# Sheet1.net
KiCad netlist of a schematic drawn in Altium Designer
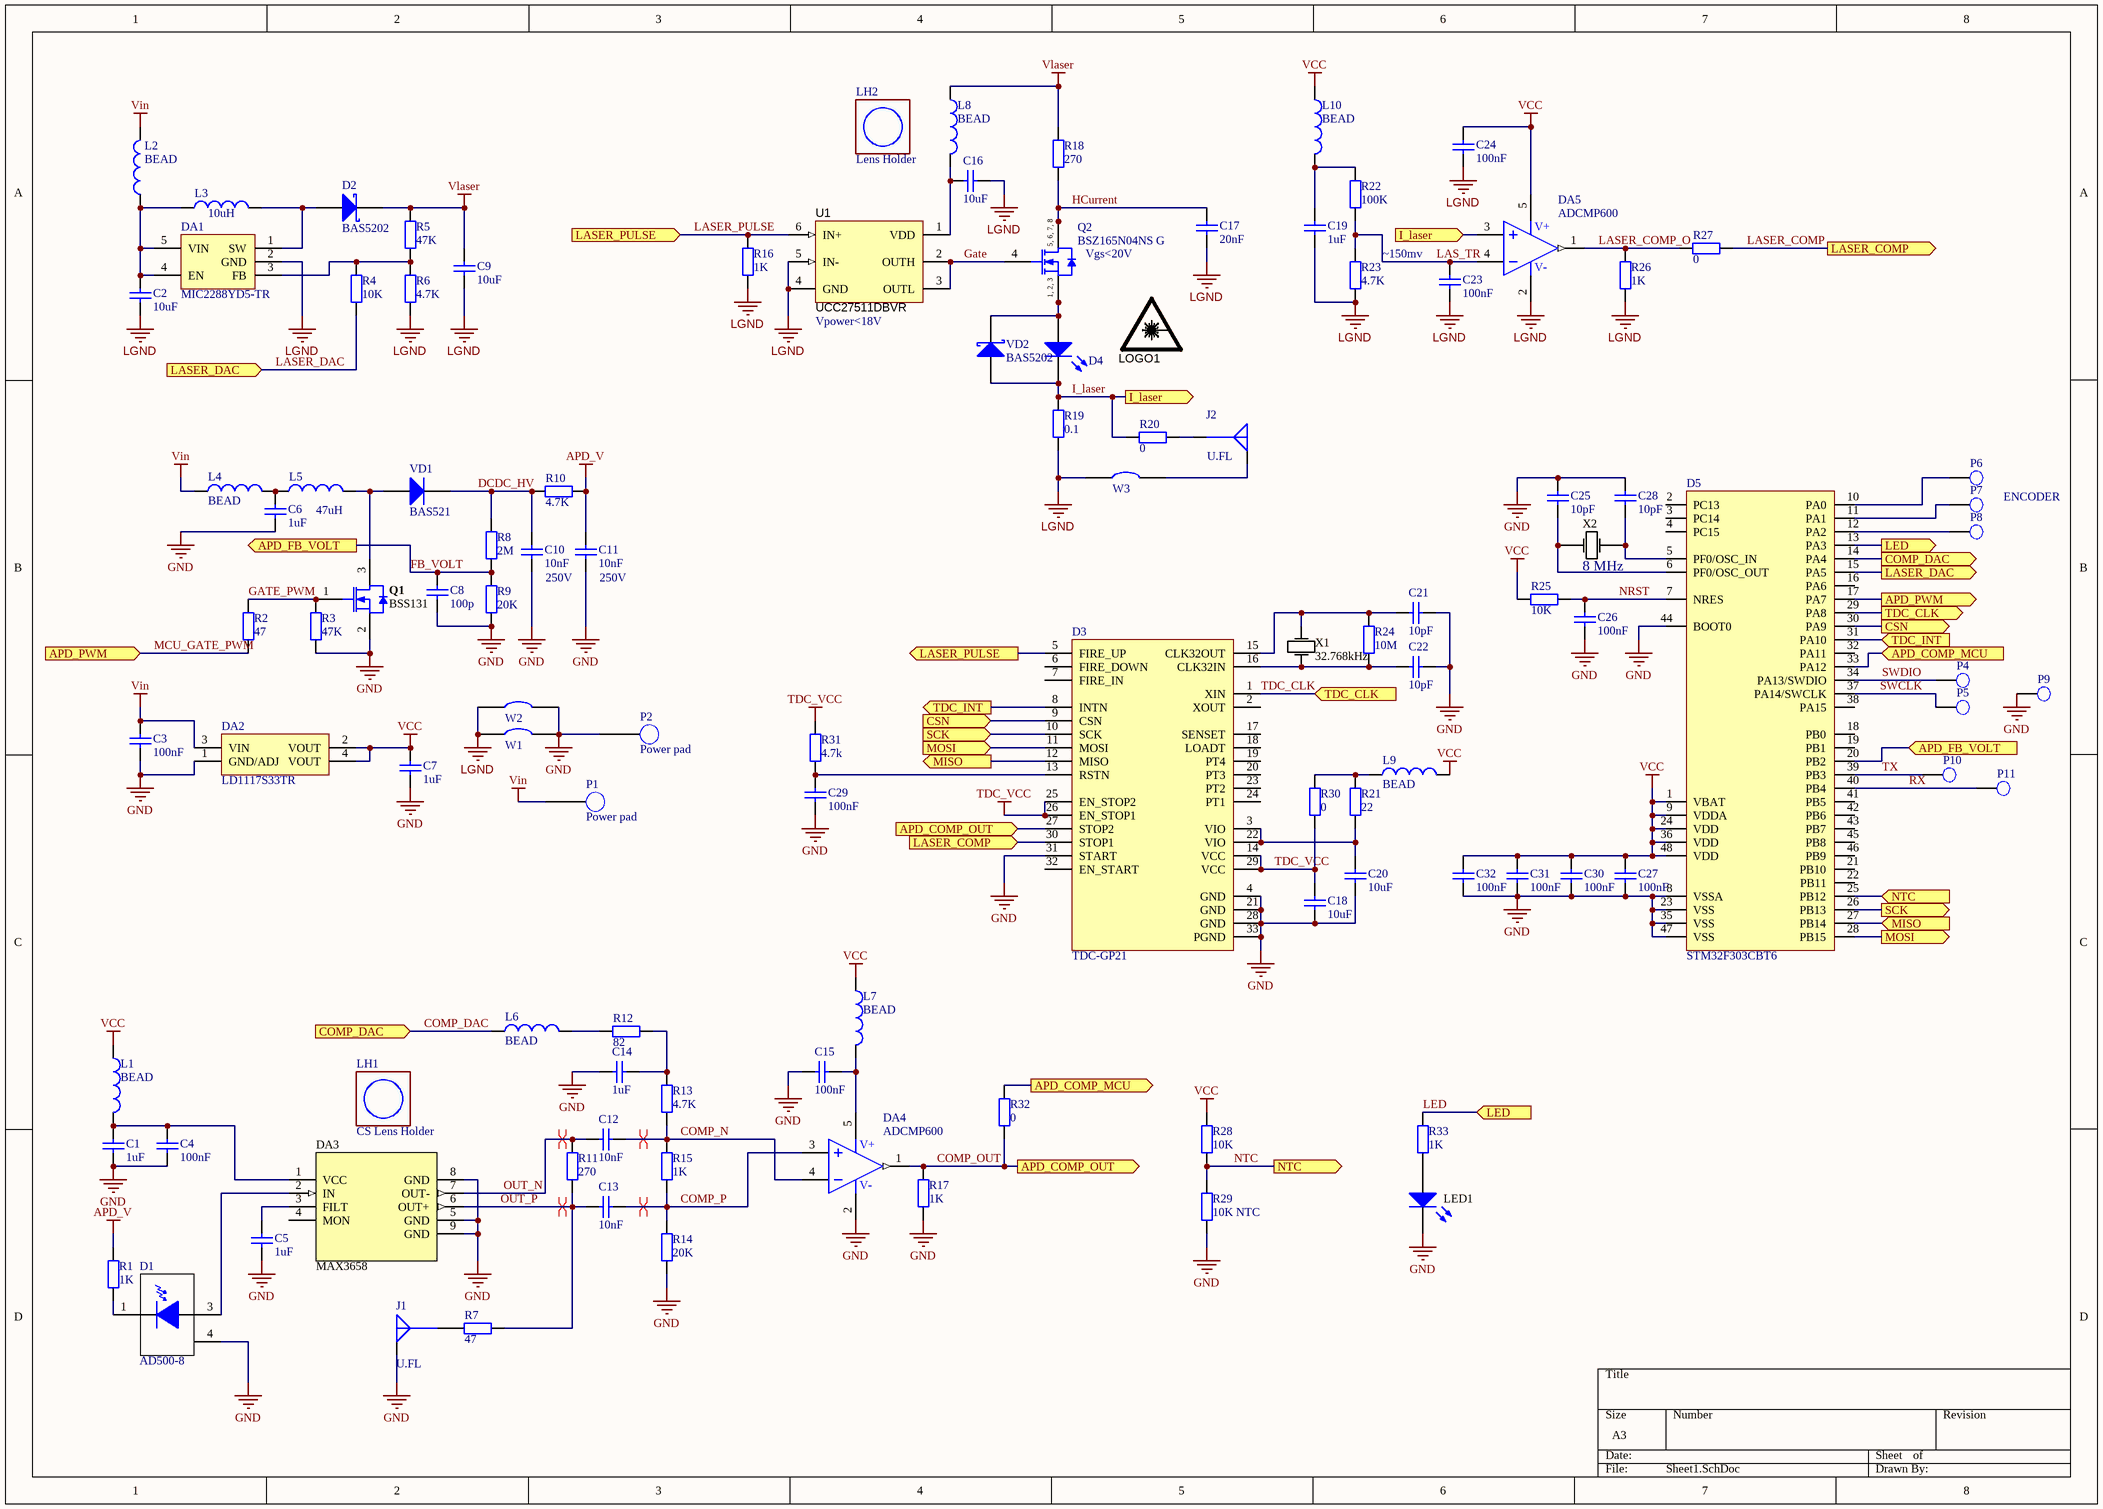
[diagram p0: Sheet1.SchDoc]

(export (version "E")
  (design (tool "Eeschema 10.0.6"))
  (components
    (comp (ref "C1")
      (value "1uF")
      (footprint "CAPC2012X135N")
      (description "Chip capacitor")
      (fields (field (name "VOLTAGE") "25V"))
      (libsource (lib "MyLibSch") (part "CC0805"))
    )
    (comp (ref "C2")
      (value "10uF")
      (footprint "CAPC1608X90N")
      (description "Chip capacitor")
      (fields (field (name "VOLTAGE") "25V"))
      (libsource (lib "MyLibSch") (part "CC0805"))
    )
    (comp (ref "C3")
      (value "100nF")
      (footprint "CAPC1608X90N")
      (description "Chip capacitor")
      (fields (field (name "VOLTAGE") "25V"))
      (libsource (lib "MyLibSch") (part "CC0805"))
    )
    (comp (ref "C4")
      (value "100nF")
      (footprint "CAPC1608X90N")
      (description "Chip capacitor")
      (fields (field (name "VOLTAGE") "25V"))
      (libsource (lib "MyLibSch") (part "CC0805"))
    )
    (comp (ref "C5")
      (value "1uF")
      (footprint "CAPC1608X90N")
      (description "Chip capacitor")
      (fields (field (name "VOLTAGE") "25V"))
      (libsource (lib "MyLibSch") (part "CC0805"))
    )
    (comp (ref "C6")
      (value "1uF")
      (footprint "CAPC2012X135N")
      (description "Chip capacitor")
      (fields (field (name "VOLTAGE") "25V"))
      (libsource (lib "MyLibSch") (part "CC0805"))
    )
    (comp (ref "C7")
      (value "1uF")
      (footprint "CAPC2012X135N")
      (description "Chip capacitor")
      (fields (field (name "VOLTAGE") "25V"))
      (libsource (lib "MyLibSch") (part "CC0805"))
    )
    (comp (ref "C8")
      (value "100p")
      (footprint "CAPC1608X90N")
      (description "Chip capacitor")
      (fields (field (name "VOLTAGE") "25V"))
      (libsource (lib "MyLibSch") (part "CC0805"))
    )
    (comp (ref "C9")
      (value "10uF")
      (footprint "CAPC1608X90N")
      (description "Chip capacitor")
      (fields (field (name "VOLTAGE") "25V"))
      (libsource (lib "MyLibSch") (part "CC0805"))
    )
    (comp (ref "C10")
      (value "10nF")
      (footprint "CAPC2012X135N")
      (description "Chip capacitor")
      (fields (field (name "VOLTAGE") "250V"))
      (libsource (lib "MyLibSch") (part "CC0805"))
    )
    (comp (ref "C11")
      (value "10nF")
      (footprint "CAPC2012X135N")
      (description "Chip capacitor")
      (fields (field (name "VOLTAGE") "250V"))
      (libsource (lib "MyLibSch") (part "CC0805"))
    )
    (comp (ref "C12")
      (value "10nF")
      (footprint "CAPC1608X90N")
      (description "Chip capacitor")
      (fields (field (name "VOLTAGE") "25V"))
      (libsource (lib "MyLibSch") (part "CC0805"))
    )
    (comp (ref "C13")
      (value "10nF")
      (footprint "CAPC1608X90N")
      (description "Chip capacitor")
      (fields (field (name "VOLTAGE") "25V"))
      (libsource (lib "MyLibSch") (part "CC0805"))
    )
    (comp (ref "C14")
      (value "1uF")
      (footprint "CAPC2012X135N")
      (description "Chip capacitor")
      (fields (field (name "VOLTAGE") "25V"))
      (libsource (lib "MyLibSch") (part "CC0805"))
    )
    (comp (ref "C15")
      (value "100nF")
      (footprint "CAPC1608X90N")
      (description "Chip capacitor")
      (fields (field (name "VOLTAGE") "25V"))
      (libsource (lib "MyLibSch") (part "CC0805"))
    )
    (comp (ref "C16")
      (value "10uF")
      (footprint "CAPC1608X90N")
      (description "Chip capacitor")
      (fields (field (name "VOLTAGE") "25V"))
      (libsource (lib "MyLibSch") (part "CC0805"))
    )
    (comp (ref "C17")
      (value "20nF")
      (footprint "CAPC1608X90N")
      (description "Chip capacitor")
      (fields (field (name "VOLTAGE") "25V"))
      (libsource (lib "MyLibSch") (part "CC0805"))
    )
    (comp (ref "C18")
      (value "10uF")
      (footprint "CAPC1608X90N")
      (description "Chip capacitor")
      (fields (field (name "VOLTAGE") "25V"))
      (libsource (lib "MyLibSch") (part "CC0805"))
    )
    (comp (ref "C19")
      (value "1uF")
      (footprint "CAPC2012X135N")
      (description "Chip capacitor")
      (fields (field (name "VOLTAGE") "25V"))
      (libsource (lib "MyLibSch") (part "CC0805"))
    )
    (comp (ref "C20")
      (value "10uF")
      (footprint "CAPC1608X90N")
      (description "Chip capacitor")
      (fields (field (name "VOLTAGE") "25V"))
      (libsource (lib "MyLibSch") (part "CC0805"))
    )
    (comp (ref "C21")
      (value "10pF")
      (footprint "CAPC1608X90N")
      (description "Chip capacitor")
      (fields (field (name "VOLTAGE") "25V"))
      (libsource (lib "MyLibSch") (part "CC0805"))
    )
    (comp (ref "C22")
      (value "10pF")
      (footprint "CAPC1608X90N")
      (description "Chip capacitor")
      (fields (field (name "VOLTAGE") "25V"))
      (libsource (lib "MyLibSch") (part "CC0805"))
    )
    (comp (ref "C23")
      (value "100nF")
      (footprint "CAPC1608X90N")
      (description "Chip capacitor")
      (fields (field (name "VOLTAGE") "25V"))
      (libsource (lib "MyLibSch") (part "CC0805"))
    )
    (comp (ref "C24")
      (value "100nF")
      (footprint "CAPC1608X90N")
      (description "Chip capacitor")
      (fields (field (name "VOLTAGE") "25V"))
      (libsource (lib "MyLibSch") (part "CC0805"))
    )
    (comp (ref "C25")
      (value "10pF")
      (footprint "CAPC1608X90N")
      (description "Chip capacitor")
      (fields (field (name "VOLTAGE") "25V"))
      (libsource (lib "MyLibSch") (part "CC0805"))
    )
    (comp (ref "C26")
      (value "100nF")
      (footprint "CAPC1608X90N")
      (description "Chip capacitor")
      (fields (field (name "VOLTAGE") "25V"))
      (libsource (lib "MyLibSch") (part "CC0805"))
    )
    (comp (ref "C27")
      (value "100nF")
      (footprint "CAPC1608X90N")
      (description "Chip capacitor")
      (fields (field (name "VOLTAGE") "25V"))
      (libsource (lib "MyLibSch") (part "CC0805"))
    )
    (comp (ref "C28")
      (value "10pF")
      (footprint "CAPC1608X90N")
      (description "Chip capacitor")
      (fields (field (name "VOLTAGE") "25V"))
      (libsource (lib "MyLibSch") (part "CC0805"))
    )
    (comp (ref "C29")
      (value "100nF")
      (footprint "CAPC1608X90N")
      (description "Chip capacitor")
      (fields (field (name "VOLTAGE") "25V"))
      (libsource (lib "MyLibSch") (part "CC0805"))
    )
    (comp (ref "C30")
      (value "100nF")
      (footprint "CAPC1608X90N")
      (description "Chip capacitor")
      (fields (field (name "VOLTAGE") "25V"))
      (libsource (lib "MyLibSch") (part "CC0805"))
    )
    (comp (ref "C31")
      (value "100nF")
      (footprint "CAPC1608X90N")
      (description "Chip capacitor")
      (fields (field (name "VOLTAGE") "25V"))
      (libsource (lib "MyLibSch") (part "CC0805"))
    )
    (comp (ref "C32")
      (value "100nF")
      (footprint "CAPC1608X90N")
      (description "Chip capacitor")
      (fields (field (name "VOLTAGE") "25V"))
      (libsource (lib "MyLibSch") (part "CC0805"))
    )
    (comp (ref "D1")
      (value "AD500-8")
      (footprint "AD500-8")
      (description "APD photodiode")
      (libsource (lib "lcd_lib") (part "AD500-8"))
    )
    (comp (ref "D2")
      (value "BAS5202")
      (footprint "SOD523F")
      (description "Schottky Diode")
      (fields (field (name "PUBLISHER") "Altium Limited"))
      (libsource (lib "Miscellaneous Devices") (part "D Schottky"))
    )
    (comp (ref "D3")
      (value "TDC-GP21")
      (footprint "QFN32 5x5mm")
      (description "TDC")
      (libsource (lib "lcd_lib") (part "TDC_GP21"))
    )
    (comp (ref "D4")
      (value "Laser")
      (footprint "SPL_PL90")
      (description "TO-18 Laser")
      (libsource (lib "lcd_lib") (part "TO-18 Laser"))
    )
    (comp (ref "D5")
      (value "STM32F303CBT6")
      (footprint "LQFP-48_N")
      (description "Microcontroller")
      (libsource (lib "lcd_lib") (part "STM32F3_LQFP48"))
    )
    (comp (ref "DA1")
      (value "MIC2288YD5-TR")
      (footprint "SOT23-5")
      (description "Step Up")
      (libsource (lib "lcd_lib") (part "MIC2288"))
    )
    (comp (ref "DA2")
      (value "LD1117S33TR")
      (footprint "SOT223")
      (description "LOW DROP FIXED AND ADJUSTABLE  POSITIVE VOLTAGE REGULATORS")
      (libsource (lib "MyLibSch") (part "LD1117S"))
    )
    (comp (ref "DA3")
      (value "MAX3658")
      (footprint "TDFN-8_0.65")
      (description "Transimpedance Amp")
      (fields (field (name "PART NUMBER") "AD7278"))
      (libsource (lib "lcd_lib") (part "MAX3658"))
    )
    (comp (ref "DA4")
      (value "ADCMP600")
      (footprint "SOT23-5")
      (description "Fast comparator")
      (libsource (lib "lcd_lib") (part "ADCMP600"))
    )
    (comp (ref "DA5")
      (value "ADCMP600")
      (footprint "SOT23-5")
      (description "Fast comparator")
      (libsource (lib "lcd_lib") (part "ADCMP600"))
    )
    (comp (ref "J1")
      (value "U.FL")
      (footprint "TE C-1909763")
      (libsource (lib "RF Connector") (part "RF Connector - SMA"))
    )
    (comp (ref "J2")
      (value "U.FL")
      (footprint "TE C-1909763")
      (libsource (lib "RF Connector") (part "RF Connector - SMA"))
    )
    (comp (ref "L1")
      (value "BEAD")
      (footprint "INDC1608N")
      (description "Ferrit Bead")
      (libsource (lib "MyLibSch") (part "BEAD"))
    )
    (comp (ref "L2")
      (value "BEAD")
      (footprint "INDC1608N")
      (description "Ferrit Bead")
      (libsource (lib "MyLibSch") (part "BEAD"))
    )
    (comp (ref "L3")
      (value "10uH")
      (footprint "MyLibPcb:V0805HD")
      (description "Inductor")
      (fields (field (name "PUBLISHER") "Altium Limited"))
      (libsource (lib "Miscellaneous Devices") (part "Inductor"))
    )
    (comp (ref "L4")
      (value "BEAD")
      (footprint "INDC1608N")
      (description "Ferrit Bead")
      (libsource (lib "MyLibSch") (part "BEAD"))
    )
    (comp (ref "L5")
      (value "47uH")
      (footprint "INDC3216")
      (description "Inductor")
      (fields (field (name "PUBLISHER") "Altium Limited"))
      (libsource (lib "Miscellaneous Devices") (part "Inductor"))
    )
    (comp (ref "L6")
      (value "BEAD")
      (footprint "INDC1608N")
      (description "Ferrit Bead")
      (libsource (lib "MyLibSch") (part "BEAD"))
    )
    (comp (ref "L7")
      (value "BEAD")
      (footprint "INDC1608N")
      (description "Ferrit Bead")
      (libsource (lib "MyLibSch") (part "BEAD"))
    )
    (comp (ref "L8")
      (value "BEAD")
      (footprint "INDC1608N")
      (description "Ferrit Bead")
      (libsource (lib "MyLibSch") (part "BEAD"))
    )
    (comp (ref "L9")
      (value "BEAD")
      (footprint "INDC1608N")
      (description "Ferrit Bead")
      (libsource (lib "MyLibSch") (part "BEAD"))
    )
    (comp (ref "L10")
      (value "BEAD")
      (footprint "INDC1608N")
      (description "Ferrit Bead")
      (libsource (lib "MyLibSch") (part "BEAD"))
    )
    (comp (ref "LED1")
      (value "LED")
      (footprint "PcbLib3:LED_0603")
      (description "LED_0603")
      (libsource (lib "lcd_lib") (part "LED_0603"))
    )
    (comp (ref "LH1")
      (value "CS Lens Holder")
      (footprint "Lens Holder CS")
      (description "M12 Lens Holder")
      (libsource (lib "lcd_lib") (part "CS Lens Holder"))
    )
    (comp (ref "LH2")
      (value "Lens Holder")
      (footprint "LENS_HOLDER_20MM_ADJ")
      (description "M12 Lens Holder")
      (libsource (lib "lcd_lib") (part "M12 Lens Holder"))
    )
    (comp (ref "LOGO1")
      (value "LASER RADIATION")
      (footprint "LaserWarning_Small")
      (description "Laser Warning Symbol")
      (fields (field (name "SYMBOLCREATOR") "a0412235") (field (name "PUBLISHER") "Texas Instruments"))
      (libsource (lib "Logos") (part "Laser_Warning"))
    )
    (comp (ref "P1")
      (value "Power pad")
      (footprint "Ext_power_pad")
      (description "Pad for wire")
      (libsource (lib "lcd_lib") (part "Power_pad"))
    )
    (comp (ref "P2")
      (value "Power pad")
      (footprint "Ext_power_pad")
      (description "Pad for wire")
      (libsource (lib "lcd_lib") (part "Power_pad"))
    )
    (comp (ref "P4")
      (value "Pad")
      (footprint "PcbLib3:Ext_pad_2")
      (description "Pad for wire")
      (libsource (lib "lcd_lib") (part "Ext Pad"))
    )
    (comp (ref "P5")
      (value "Pad")
      (footprint "PcbLib3:Ext_pad_2")
      (description "Pad for wire")
      (libsource (lib "lcd_lib") (part "Ext Pad"))
    )
    (comp (ref "P6")
      (value "Pad")
      (footprint "PcbLib3:Ext_pad_2")
      (description "Pad for wire")
      (libsource (lib "lcd_lib") (part "Ext Pad"))
    )
    (comp (ref "P7")
      (value "Pad")
      (footprint "PcbLib3:Ext_pad_2")
      (description "Pad for wire")
      (libsource (lib "lcd_lib") (part "Ext Pad"))
    )
    (comp (ref "P8")
      (value "Pad")
      (footprint "PcbLib3:Ext_pad_2")
      (description "Pad for wire")
      (libsource (lib "lcd_lib") (part "Ext Pad"))
    )
    (comp (ref "P9")
      (value "Pad")
      (footprint "PcbLib3:Ext_pad_2")
      (description "Pad for wire")
      (libsource (lib "lcd_lib") (part "Ext Pad"))
    )
    (comp (ref "P10")
      (value "Pad")
      (footprint "PcbLib3:Ext_pad_2")
      (description "Pad for wire")
      (libsource (lib "lcd_lib") (part "Ext Pad"))
    )
    (comp (ref "P11")
      (value "Pad")
      (footprint "PcbLib3:Ext_pad_2")
      (description "Pad for wire")
      (libsource (lib "lcd_lib") (part "Ext Pad"))
    )
    (comp (ref "Q1")
      (value "BSS131")
      (footprint "INF-PG-SOT23_N")
      (fields (field (name "MANUFACTURER") "Infineon"))
      (libsource (lib "altium-import") (part "root_0_BSS131_"))
    )
    (comp (ref "Q2")
      (value "BSZ165N04NS G")
      (footprint "INF-PG-TSDSON-8-1_A_V")
      (fields (field (name "MANUFACTURER") "Infineon"))
      (libsource (lib "BSZ165N04NS G") (part "BSZ165N04NS G"))
    )
    (comp (ref "R1")
      (value "1K")
      (footprint "RESC1608X55N")
      (description "Chip resistor")
      (fields (field (name "TOLERANCE") "5%"))
      (libsource (lib "MyLibSch") (part "RC0805"))
    )
    (comp (ref "R2")
      (value "47")
      (footprint "RESC1608X55N")
      (description "Chip resistor")
      (fields (field (name "TOLERANCE") "5%"))
      (libsource (lib "MyLibSch") (part "RC0805"))
    )
    (comp (ref "R3")
      (value "47K")
      (footprint "RESC1608X55N")
      (description "Chip resistor")
      (fields (field (name "TOLERANCE") "5%"))
      (libsource (lib "") (part "RC0805_1"))
    )
    (comp (ref "R4")
      (value "10K")
      (footprint "RESC1608X55N")
      (description "Chip resistor")
      (fields (field (name "TOLERANCE") "5%"))
      (libsource (lib "MyLibSch") (part "RC0805"))
    )
    (comp (ref "R5")
      (value "47K")
      (footprint "RESC1608X55N")
      (description "Chip resistor")
      (fields (field (name "TOLERANCE") "5%"))
      (libsource (lib "MyLibSch") (part "RC0805"))
    )
    (comp (ref "R6")
      (value "4.7K")
      (footprint "RESC1608X55N")
      (description "Chip resistor")
      (fields (field (name "TOLERANCE") "5%"))
      (libsource (lib "MyLibSch") (part "RC0805"))
    )
    (comp (ref "R7")
      (value "47")
      (footprint "RESC1608X55N")
      (description "Chip resistor")
      (fields (field (name "TOLERANCE") "5%"))
      (libsource (lib "MyLibSch") (part "RC0805"))
    )
    (comp (ref "R8")
      (value "2M")
      (footprint "RESC2012X70N")
      (description "Chip resistor")
      (fields (field (name "TOLERANCE") "5%"))
      (libsource (lib "MyLibSch") (part "RC0805"))
    )
    (comp (ref "R9")
      (value "20K")
      (footprint "RESC1608X55N")
      (description "Chip resistor")
      (fields (field (name "TOLERANCE") "5%"))
      (libsource (lib "") (part "RC0805_1"))
    )
    (comp (ref "R10")
      (value "4.7K")
      (footprint "RESC1608X55N")
      (description "Chip resistor")
      (fields (field (name "TOLERANCE") "5%"))
      (libsource (lib "") (part "RC0805_2"))
    )
    (comp (ref "R11")
      (value "270")
      (footprint "RESC1608X55N")
      (description "Chip resistor")
      (fields (field (name "TOLERANCE") "5%"))
      (libsource (lib "MyLibSch") (part "RC0805"))
    )
    (comp (ref "R12")
      (value "82")
      (footprint "RESC1608X55N")
      (description "Chip resistor")
      (fields (field (name "TOLERANCE") "5%"))
      (libsource (lib "") (part "RC0805_2"))
    )
    (comp (ref "R13")
      (value "4.7K")
      (footprint "RESC1608X55N")
      (description "Chip resistor")
      (fields (field (name "TOLERANCE") "5%"))
      (libsource (lib "MyLibSch") (part "RC0805"))
    )
    (comp (ref "R14")
      (value "20K")
      (footprint "RESC2012X70N")
      (description "Chip resistor")
      (fields (field (name "TOLERANCE") "5%"))
      (libsource (lib "MyLibSch") (part "RC0805"))
    )
    (comp (ref "R15")
      (value "1K")
      (footprint "RESC1608X55N")
      (description "Chip resistor")
      (fields (field (name "TOLERANCE") "5%"))
      (libsource (lib "MyLibSch") (part "RC0805"))
    )
    (comp (ref "R16")
      (value "1K")
      (footprint "RESC1608X55N")
      (description "Chip resistor")
      (fields (field (name "TOLERANCE") "5%"))
      (libsource (lib "MyLibSch") (part "RC0805"))
    )
    (comp (ref "R17")
      (value "1K")
      (footprint "RESC1608X55N")
      (description "Chip resistor")
      (fields (field (name "TOLERANCE") "5%"))
      (libsource (lib "MyLibSch") (part "RC0805"))
    )
    (comp (ref "R18")
      (value "270")
      (footprint "RESC1608X55N")
      (description "Chip resistor")
      (fields (field (name "TOLERANCE") "5%"))
      (libsource (lib "MyLibSch") (part "RC0805"))
    )
    (comp (ref "R19")
      (value "0.1")
      (footprint "RESC2012X70N")
      (description "Chip resistor")
      (fields (field (name "TOLERANCE") "5%"))
      (libsource (lib "MyLibSch") (part "RC0805"))
    )
    (comp (ref "R20")
      (value "0")
      (footprint "RESC1608X55N")
      (description "Chip resistor")
      (fields (field (name "TOLERANCE") "5%"))
      (libsource (lib "") (part "RC0805_2"))
    )
    (comp (ref "R21")
      (value "22")
      (footprint "RESC1608X55N")
      (description "Chip resistor")
      (fields (field (name "TOLERANCE") "5%"))
      (libsource (lib "") (part "RC0805_1"))
    )
    (comp (ref "R22")
      (value "100K")
      (footprint "RESC1608X55N")
      (description "Chip resistor")
      (fields (field (name "TOLERANCE") "5%"))
      (libsource (lib "") (part "RC0805_1"))
    )
    (comp (ref "R23")
      (value "4.7K")
      (footprint "RESC1608X55N")
      (description "Chip resistor")
      (fields (field (name "TOLERANCE") "5%"))
      (libsource (lib "") (part "RC0805_1"))
    )
    (comp (ref "R24")
      (value "10M")
      (footprint "RESC1608X55N")
      (description "Chip resistor")
      (fields (field (name "TOLERANCE") "5%"))
      (libsource (lib "MyLibSch") (part "RC0805"))
    )
    (comp (ref "R25")
      (value "10K")
      (footprint "RESC1608X55N")
      (description "Chip resistor")
      (fields (field (name "TOLERANCE") "5%"))
      (libsource (lib "") (part "RC0805_3"))
    )
    (comp (ref "R26")
      (value "1K")
      (footprint "RESC1608X55N")
      (description "Chip resistor")
      (fields (field (name "TOLERANCE") "5%"))
      (libsource (lib "MyLibSch") (part "RC0805"))
    )
    (comp (ref "R27")
      (value "0")
      (footprint "RESC1608X55N")
      (description "Chip resistor")
      (fields (field (name "TOLERANCE") "5%"))
      (libsource (lib "") (part "RC0805_3"))
    )
    (comp (ref "R28")
      (value "10K")
      (footprint "RESC1608X55N")
      (description "Chip resistor")
      (fields (field (name "TOLERANCE") "5%"))
      (libsource (lib "") (part "RC0805_1"))
    )
    (comp (ref "R29")
      (value "10K NTC")
      (footprint "RESC1608X55N")
      (description "Chip resistor")
      (fields (field (name "TOLERANCE") "5%"))
      (libsource (lib "MyLibSch") (part "RC0805"))
    )
    (comp (ref "R30")
      (value "0")
      (footprint "RESC1608X55N")
      (description "Chip resistor")
      (fields (field (name "TOLERANCE") "5%"))
      (libsource (lib "") (part "RC0805_1"))
    )
    (comp (ref "R31")
      (value "4.7k")
      (footprint "RESC1608X55N")
      (description "Chip resistor")
      (fields (field (name "TOLERANCE") "5%"))
      (libsource (lib "") (part "RC0805_1"))
    )
    (comp (ref "R32")
      (value "0")
      (footprint "RESC1608X55N")
      (description "Chip resistor")
      (fields (field (name "TOLERANCE") "5%"))
      (libsource (lib "") (part "RC0805_1"))
    )
    (comp (ref "R33")
      (value "1K")
      (footprint "RESC1608X55N")
      (description "Chip resistor")
      (fields (field (name "TOLERANCE") "5%"))
      (libsource (lib "MyLibSch") (part "RC0805"))
    )
    (comp (ref "U1")
      (value "UCC27511DBVR")
      (footprint "Miscellaneous Devices:SOT23-6_M")
      (description "Single-Channel High-Speed Low-Side Gate Driver (with 4-A Peak Source and 8-A Peak Sink), DBV0006A")
      (fields
        (field (name "ALTERNATE PARTNUMBER") "UCC27511DBVT")
        (field (name "MANUFACTURER") "Texas Instruments")
        (field (name "SYMBOLCREATOR") "a0411947")
        (field (name "PUBLISHER") "Texas Instruments")
      )
      (libsource (lib "TI_Pre_Release") (part "UCC27511DBVR"))
    )
    (comp (ref "VD1")
      (value "BAS521")
      (footprint "SOD523F")
      (libsource (lib "MyLibSch") (part "DIODE 2 pin"))
    )
    (comp (ref "VD2")
      (value "BAS5202")
      (footprint "SOD523F")
      (description "Schottky Diode")
      (fields (field (name "PUBLISHER") "Altium Limited"))
      (libsource (lib "Miscellaneous Devices") (part "D Schottky"))
    )
    (comp (ref "W1")
      (value "NET connector")
      (footprint "Net connector")
      (libsource (lib "lcd_lib") (part "NET connector"))
    )
    (comp (ref "W2")
      (value "NET connector")
      (footprint "Net connector")
      (libsource (lib "lcd_lib") (part "NET connector"))
    )
    (comp (ref "W3")
      (value "NET connector")
      (footprint "Net connector")
      (libsource (lib "lcd_lib") (part "NET connector"))
    )
    (comp (ref "X1")
      (value "32.768kHz")
      (footprint "QUARTZ_32K")
      (description "Quartz")
      (libsource (lib "lcd_lib") (part "Quartz_32k"))
    )
    (comp (ref "X2")
      (value "8 MHz")
      (footprint "SX-6 QUARTZ")
      (description "Quartz_SX-6 (SMD06035C4)")
      (fields (field (name "Comment") "Quartz"))
      (libsource (lib "lcd_lib") (part "Quartz_SX-6"))
    )
  )
  (nets
    (net (code "1") (name "/APD_COMP_MCU") (class "Default")
      (node (ref "D5") (pin "33") (pinfunction "PA12_33") (pintype "passive"))
      (node (ref "R32") (pin "1") (pinfunction "1_1") (pintype "passive"))
    )
    (net (code "2") (name "/COMP_DAC") (class "Default")
      (node (ref "D5") (pin "14") (pinfunction "PA4_14") (pintype "passive"))
      (node (ref "L6") (pin "1") (pinfunction "1_1") (pintype "passive"))
    )
    (net (code "3") (name "/COMP_N") (class "Default")
      (node (ref "C12") (pin "1") (pinfunction "1_1") (pintype "passive"))
      (node (ref "DA4") (pin "4") (pinfunction "IN-_4") (pintype "passive"))
      (node (ref "R13") (pin "1") (pinfunction "1_1") (pintype "passive"))
      (node (ref "R15") (pin "2") (pinfunction "2_2") (pintype "passive"))
    )
    (net (code "4") (name "/COMP_OUT") (class "Default")
      (node (ref "D3") (pin "27") (pinfunction "STOP2_27") (pintype "passive"))
      (node (ref "DA4") (pin "1") (pinfunction "OUT_1") (pintype "output"))
      (node (ref "R17") (pin "2") (pinfunction "2_2") (pintype "passive"))
      (node (ref "R32") (pin "2") (pinfunction "2_2") (pintype "passive"))
    )
    (net (code "5") (name "/COMP_P") (class "Default")
      (node (ref "C13") (pin "1") (pinfunction "1_1") (pintype "passive"))
      (node (ref "DA4") (pin "3") (pinfunction "IN+_3") (pintype "passive"))
      (node (ref "R14") (pin "2") (pinfunction "2_2") (pintype "passive"))
      (node (ref "R15") (pin "1") (pinfunction "1_1") (pintype "passive"))
    )
    (net (code "6") (name "/CSN") (class "Default")
      (node (ref "D3") (pin "9") (pinfunction "CSN_9") (pintype "passive"))
      (node (ref "D5") (pin "30") (pinfunction "PA9_30") (pintype "passive"))
    )
    (net (code "7") (name "/DCDC_HV") (class "Default")
      (node (ref "C10") (pin "2") (pinfunction "2_2") (pintype "passive"))
      (node (ref "R10") (pin "2") (pinfunction "2_2") (pintype "passive"))
      (node (ref "R8") (pin "2") (pinfunction "2_2") (pintype "passive"))
      (node (ref "VD1") (pin "K") (pinfunction "K_K") (pintype "passive"))
    )
    (net (code "8") (name "/FB_VOLT") (class "Default")
      (node (ref "C8") (pin "1") (pinfunction "1_1") (pintype "passive"))
      (node (ref "D5") (pin "20") (pinfunction "PB2_20") (pintype "passive"))
      (node (ref "R8") (pin "1") (pinfunction "1_1") (pintype "passive"))
      (node (ref "R9") (pin "1") (pinfunction "1_1") (pintype "passive"))
    )
    (net (code "9") (name "/GATE_PWM") (class "Default")
      (node (ref "Q1") (pin "1") (pinfunction "GATE_1") (pintype "passive"))
      (node (ref "R2") (pin "2") (pinfunction "2_2") (pintype "passive"))
      (node (ref "R3") (pin "1") (pinfunction "1_1") (pintype "passive"))
    )
    (net (code "10") (name "/Gate") (class "Default")
      (node (ref "Q2") (pin "4") (pinfunction "GATE_4") (pintype "passive"))
      (node (ref "U1") (pin "2") (pinfunction "OUTH_2") (pintype "power_in"))
      (node (ref "U1") (pin "3") (pinfunction "OUTL_3") (pintype "power_in"))
    )
    (net (code "11") (name "/HCurrent") (class "Default")
      (node (ref "C17") (pin "2") (pinfunction "2_2") (pintype "passive"))
      (node (ref "Q2") (pin "5") (pinfunction "DRAIN_5") (pintype "passive"))
      (node (ref "Q2") (pin "6") (pinfunction "DRAIN_6") (pintype "passive"))
      (node (ref "Q2") (pin "7") (pinfunction "DRAIN_7") (pintype "passive"))
      (node (ref "Q2") (pin "8") (pinfunction "DRAIN_8") (pintype "passive"))
      (node (ref "R18") (pin "1") (pinfunction "1_1") (pintype "passive"))
    )
    (net (code "12") (name "/I_laser") (class "Default")
      (node (ref "D4") (pin "K") (pinfunction "K_K") (pintype "passive"))
      (node (ref "DA5") (pin "3") (pinfunction "IN+_3") (pintype "passive"))
      (node (ref "R19") (pin "2") (pinfunction "2_2") (pintype "passive"))
      (node (ref "R20") (pin "2") (pinfunction "2_2") (pintype "passive"))
      (node (ref "VD2") (pin "A") (pinfunction "A_A") (pintype "passive"))
    )
    (net (code "13") (name "/LASER_COMP") (class "Default")
      (node (ref "D3") (pin "30") (pinfunction "STOP1_30") (pintype "passive"))
      (node (ref "R27") (pin "2") (pinfunction "2_2") (pintype "passive"))
    )
    (net (code "14") (name "/LASER_COMP_O") (class "Default")
      (node (ref "DA5") (pin "1") (pinfunction "OUT_1") (pintype "output"))
      (node (ref "R26") (pin "2") (pinfunction "2_2") (pintype "passive"))
      (node (ref "R27") (pin "1") (pinfunction "1_1") (pintype "passive"))
    )
    (net (code "15") (name "/LASER_DAC") (class "Default")
      (node (ref "D5") (pin "15") (pinfunction "PA5_15") (pintype "passive"))
      (node (ref "R4") (pin "1") (pinfunction "1_1") (pintype "passive"))
    )
    (net (code "16") (name "/LASER_PULSE") (class "Default")
      (node (ref "D3") (pin "5") (pinfunction "FIRE_UP_5") (pintype "passive"))
      (node (ref "R16") (pin "2") (pinfunction "2_2") (pintype "passive"))
      (node (ref "U1") (pin "6") (pinfunction "IN+_6") (pintype "input"))
    )
    (net (code "17") (name "/LAS_TR") (class "Default")
      (node (ref "C23") (pin "2") (pinfunction "2_2") (pintype "passive"))
      (node (ref "DA5") (pin "4") (pinfunction "IN-_4") (pintype "passive"))
      (node (ref "R22") (pin "2") (pinfunction "2_2") (pintype "passive"))
      (node (ref "R23") (pin "1") (pinfunction "1_1") (pintype "passive"))
    )
    (net (code "18") (name "/LED") (class "Default")
      (node (ref "D5") (pin "13") (pinfunction "PA3_13") (pintype "passive"))
      (node (ref "R33") (pin "2") (pinfunction "2_2") (pintype "passive"))
    )
    (net (code "19") (name "/MCU_GATE_PWM") (class "Default")
      (node (ref "D5") (pin "17") (pinfunction "PA7_17") (pintype "passive"))
      (node (ref "R2") (pin "1") (pinfunction "1_1") (pintype "passive"))
    )
    (net (code "20") (name "/MISO") (class "Default")
      (node (ref "D3") (pin "12") (pinfunction "MISO_12") (pintype "passive"))
      (node (ref "D5") (pin "27") (pinfunction "PB14_27") (pintype "passive"))
    )
    (net (code "21") (name "/MOSI") (class "Default")
      (node (ref "D3") (pin "11") (pinfunction "MOSI_11") (pintype "passive"))
      (node (ref "D5") (pin "28") (pinfunction "PB15_28") (pintype "passive"))
    )
    (net (code "22") (name "/NRST") (class "Default")
      (node (ref "C26") (pin "2") (pinfunction "2_2") (pintype "passive"))
      (node (ref "D5") (pin "7") (pinfunction "NRES_7") (pintype "passive"))
      (node (ref "R25") (pin "2") (pinfunction "2_2") (pintype "passive"))
    )
    (net (code "23") (name "/NTC") (class "Default")
      (node (ref "D5") (pin "25") (pinfunction "PB12_25") (pintype "passive"))
      (node (ref "R28") (pin "2") (pinfunction "2_2") (pintype "passive"))
      (node (ref "R29") (pin "2") (pinfunction "2_2") (pintype "passive"))
    )
    (net (code "24") (name "/OUT_N") (class "Default")
      (node (ref "C12") (pin "2") (pinfunction "2_2") (pintype "passive"))
      (node (ref "DA3") (pin "7") (pinfunction "OUT-_7") (pintype "output"))
      (node (ref "R11") (pin "2") (pinfunction "2_2") (pintype "passive"))
    )
    (net (code "25") (name "/OUT_P") (class "Default")
      (node (ref "C13") (pin "2") (pinfunction "2_2") (pintype "passive"))
      (node (ref "DA3") (pin "6") (pinfunction "OUT+_6") (pintype "output"))
      (node (ref "R11") (pin "1") (pinfunction "1_1") (pintype "passive"))
      (node (ref "R7") (pin "2") (pinfunction "2_2") (pintype "passive"))
    )
    (net (code "26") (name "/RX") (class "Default")
      (node (ref "D5") (pin "40") (pinfunction "PB4_40") (pintype "passive"))
      (node (ref "P11") (pin "1") (pinfunction "Pad_1") (pintype "passive"))
    )
    (net (code "27") (name "/SCK") (class "Default")
      (node (ref "D3") (pin "10") (pinfunction "SCK_10") (pintype "passive"))
      (node (ref "D5") (pin "26") (pinfunction "PB13_26") (pintype "passive"))
    )
    (net (code "28") (name "/SWCLK") (class "Default")
      (node (ref "D5") (pin "37") (pinfunction "PA14/SWCLK_37") (pintype "passive"))
      (node (ref "P5") (pin "1") (pinfunction "Pad_1") (pintype "passive"))
    )
    (net (code "29") (name "/SWDIO") (class "Default")
      (node (ref "D5") (pin "34") (pinfunction "PA13/SWDIO_34") (pintype "passive"))
      (node (ref "P4") (pin "1") (pinfunction "Pad_1") (pintype "passive"))
    )
    (net (code "30") (name "/TDC_CLK") (class "Default")
      (node (ref "D3") (pin "1") (pinfunction "XIN_1") (pintype "passive"))
      (node (ref "D5") (pin "29") (pinfunction "PA8_29") (pintype "passive"))
    )
    (net (code "31") (name "/TDC_INT") (class "Default")
      (node (ref "D3") (pin "8") (pinfunction "INTN_8") (pintype "passive"))
      (node (ref "D5") (pin "31") (pinfunction "PA10_31") (pintype "passive"))
    )
    (net (code "32") (name "/TX") (class "Default")
      (node (ref "D5") (pin "39") (pinfunction "PB3_39") (pintype "passive"))
      (node (ref "P10") (pin "1") (pinfunction "Pad_1") (pintype "passive"))
    )
    (net (code "33") (name "APD_V") (class "Default")
      (node (ref "C11") (pin "2") (pinfunction "2_2") (pintype "passive"))
      (node (ref "R1") (pin "2") (pinfunction "2_2") (pintype "passive"))
      (node (ref "R10") (pin "1") (pinfunction "1_1") (pintype "passive"))
    )
    (net (code "34") (name "GND") (class "Default")
      (node (ref "C1") (pin "1") (pinfunction "1_1") (pintype "passive"))
      (node (ref "C10") (pin "1") (pinfunction "1_1") (pintype "passive"))
      (node (ref "C11") (pin "1") (pinfunction "1_1") (pintype "passive"))
      (node (ref "C14") (pin "2") (pinfunction "2_2") (pintype "passive"))
      (node (ref "C15") (pin "2") (pinfunction "2_2") (pintype "passive"))
      (node (ref "C18") (pin "1") (pinfunction "1_1") (pintype "passive"))
      (node (ref "C20") (pin "1") (pinfunction "1_1") (pintype "passive"))
      (node (ref "C21") (pin "1") (pinfunction "1_1") (pintype "passive"))
      (node (ref "C22") (pin "1") (pinfunction "1_1") (pintype "passive"))
      (node (ref "C25") (pin "2") (pinfunction "2_2") (pintype "passive"))
      (node (ref "C26") (pin "1") (pinfunction "1_1") (pintype "passive"))
      (node (ref "C27") (pin "1") (pinfunction "1_1") (pintype "passive"))
      (node (ref "C28") (pin "2") (pinfunction "2_2") (pintype "passive"))
      (node (ref "C29") (pin "1") (pinfunction "1_1") (pintype "passive"))
      (node (ref "C3") (pin "1") (pinfunction "1_1") (pintype "passive"))
      (node (ref "C30") (pin "1") (pinfunction "1_1") (pintype "passive"))
      (node (ref "C31") (pin "1") (pinfunction "1_1") (pintype "passive"))
      (node (ref "C32") (pin "1") (pinfunction "1_1") (pintype "passive"))
      (node (ref "C4") (pin "1") (pinfunction "1_1") (pintype "passive"))
      (node (ref "C5") (pin "1") (pinfunction "1_1") (pintype "passive"))
      (node (ref "C6") (pin "2") (pinfunction "2_2") (pintype "passive"))
      (node (ref "C7") (pin "1") (pinfunction "1_1") (pintype "passive"))
      (node (ref "C8") (pin "2") (pinfunction "2_2") (pintype "passive"))
      (node (ref "D1") (pin "4") (pinfunction "CASE_4") (pintype "passive"))
      (node (ref "D3") (pin "21") (pinfunction "GND_21") (pintype "passive"))
      (node (ref "D3") (pin "28") (pinfunction "GND_28") (pintype "passive"))
      (node (ref "D3") (pin "31") (pinfunction "START_31") (pintype "passive"))
      (node (ref "D3") (pin "33") (pinfunction "PGND_33") (pintype "passive"))
      (node (ref "D3") (pin "4") (pinfunction "GND_4") (pintype "passive"))
      (node (ref "D5") (pin "23") (pinfunction "VSS_23") (pintype "passive"))
      (node (ref "D5") (pin "35") (pinfunction "VSS_35") (pintype "passive"))
      (node (ref "D5") (pin "44") (pinfunction "BOOT0_44") (pintype "passive"))
      (node (ref "D5") (pin "47") (pinfunction "VSS_47") (pintype "passive"))
      (node (ref "D5") (pin "8") (pinfunction "VSSA_8") (pintype "passive"))
      (node (ref "DA2") (pin "1") (pinfunction "GND/ADJ_1") (pintype "power_in"))
      (node (ref "DA3") (pin "5") (pinfunction "GND_5") (pintype "power_in"))
      (node (ref "DA3") (pin "8") (pinfunction "GND_8") (pintype "power_in"))
      (node (ref "DA3") (pin "9") (pinfunction "GND_9") (pintype "power_in"))
      (node (ref "DA4") (pin "2") (pinfunction "V-_2") (pintype "power_in"))
      (node (ref "J1") (pin "G") (pinfunction "G_G") (pintype "passive"))
      (node (ref "LED1") (pin "2") (pinfunction "K_2") (pintype "passive"))
      (node (ref "P2") (pin "1") (pinfunction "47_1") (pintype "passive"))
      (node (ref "P9") (pin "1") (pinfunction "Pad_1") (pintype "passive"))
      (node (ref "Q1") (pin "2") (pinfunction "SOURCE_2") (pintype "passive"))
      (node (ref "R14") (pin "1") (pinfunction "1_1") (pintype "passive"))
      (node (ref "R17") (pin "1") (pinfunction "1_1") (pintype "passive"))
      (node (ref "R29") (pin "1") (pinfunction "1_1") (pintype "passive"))
      (node (ref "R3") (pin "2") (pinfunction "2_2") (pintype "passive"))
      (node (ref "R9") (pin "2") (pinfunction "2_2") (pintype "passive"))
      (node (ref "W1") (pin "2") (pinfunction "2_2") (pintype "passive"))
      (node (ref "W2") (pin "2") (pinfunction "2_2") (pintype "passive"))
    )
    (net (code "35") (name "LGND") (class "Default")
      (node (ref "C16") (pin "1") (pinfunction "1_1") (pintype "passive"))
      (node (ref "C17") (pin "1") (pinfunction "1_1") (pintype "passive"))
      (node (ref "C19") (pin "1") (pinfunction "1_1") (pintype "passive"))
      (node (ref "C2") (pin "1") (pinfunction "1_1") (pintype "passive"))
      (node (ref "C23") (pin "1") (pinfunction "1_1") (pintype "passive"))
      (node (ref "C24") (pin "1") (pinfunction "1_1") (pintype "passive"))
      (node (ref "C9") (pin "1") (pinfunction "1_1") (pintype "passive"))
      (node (ref "DA1") (pin "2") (pinfunction "GND_2") (pintype "power_in"))
      (node (ref "DA5") (pin "2") (pinfunction "V-_2") (pintype "power_in"))
      (node (ref "R16") (pin "1") (pinfunction "1_1") (pintype "passive"))
      (node (ref "R19") (pin "1") (pinfunction "1_1") (pintype "passive"))
      (node (ref "R23") (pin "2") (pinfunction "2_2") (pintype "passive"))
      (node (ref "R26") (pin "1") (pinfunction "1_1") (pintype "passive"))
      (node (ref "R6") (pin "1") (pinfunction "1_1") (pintype "passive"))
      (node (ref "U1") (pin "4") (pinfunction "GND_4") (pintype "power_in"))
      (node (ref "U1") (pin "5") (pinfunction "IN-_5") (pintype "input"))
      (node (ref "W1") (pin "1") (pinfunction "1_1") (pintype "passive"))
      (node (ref "W2") (pin "1") (pinfunction "1_1") (pintype "passive"))
      (node (ref "W3") (pin "1") (pinfunction "1_1") (pintype "passive"))
    )
    (net (code "36") (name "Net-(C6-Pad1)") (class "Default")
      (node (ref "C6") (pin "1") (pinfunction "1_1") (pintype "passive"))
      (node (ref "L4") (pin "2") (pinfunction "2_2") (pintype "passive"))
      (node (ref "L5") (pin "1") (pinfunction "1_1") (pintype "passive"))
    )
    (net (code "37") (name "Net-(C14-Pad1)") (class "Default")
      (node (ref "C14") (pin "1") (pinfunction "1_1") (pintype "passive"))
      (node (ref "R12") (pin "1") (pinfunction "1_1") (pintype "passive"))
      (node (ref "R13") (pin "2") (pinfunction "2_2") (pintype "passive"))
    )
    (net (code "38") (name "Net-(C19-Pad2)") (class "Default")
      (node (ref "C19") (pin "2") (pinfunction "2_2") (pintype "passive"))
      (node (ref "L10") (pin "2") (pinfunction "2_2") (pintype "passive"))
      (node (ref "R22") (pin "1") (pinfunction "1_1") (pintype "passive"))
    )
    (net (code "39") (name "Net-(C20-Pad2)") (class "Default")
      (node (ref "C20") (pin "2") (pinfunction "2_2") (pintype "passive"))
      (node (ref "D3") (pin "22") (pinfunction "VIO_22") (pintype "passive"))
      (node (ref "D3") (pin "3") (pinfunction "VIO_3") (pintype "passive"))
      (node (ref "R21") (pin "2") (pinfunction "2_2") (pintype "passive"))
    )
    (net (code "40") (name "Net-(D1-A)") (class "Default")
      (node (ref "D1") (pin "3") (pinfunction "A_3") (pintype "passive"))
      (node (ref "DA3") (pin "2") (pinfunction "IN_2") (pintype "input"))
    )
    (net (code "41") (name "Net-(D1-C)") (class "Default")
      (node (ref "D1") (pin "1") (pinfunction "C_1") (pintype "passive"))
      (node (ref "R1") (pin "1") (pinfunction "1_1") (pintype "passive"))
    )
    (net (code "42") (name "Net-(D3-CLK32IN)") (class "Default")
      (node (ref "C22") (pin "2") (pinfunction "2_2") (pintype "passive"))
      (node (ref "D3") (pin "16") (pinfunction "CLK32IN_16") (pintype "passive"))
      (node (ref "R24") (pin "1") (pinfunction "1_1") (pintype "passive"))
      (node (ref "X1") (pin "2") (pinfunction "2_2") (pintype "passive"))
    )
    (net (code "43") (name "Net-(D3-CLK32OUT)") (class "Default")
      (node (ref "C21") (pin "2") (pinfunction "2_2") (pintype "passive"))
      (node (ref "D3") (pin "15") (pinfunction "CLK32OUT_15") (pintype "passive"))
      (node (ref "R24") (pin "2") (pinfunction "2_2") (pintype "passive"))
      (node (ref "X1") (pin "1") (pinfunction "1_1") (pintype "passive"))
    )
    (net (code "44") (name "Net-(D3-RSTN)") (class "Default")
      (node (ref "C29") (pin "2") (pinfunction "2_2") (pintype "passive"))
      (node (ref "D3") (pin "13") (pinfunction "RSTN_13") (pintype "passive"))
      (node (ref "R31") (pin "2") (pinfunction "2_2") (pintype "passive"))
    )
    (net (code "45") (name "Net-(D4-PadA)") (class "Default")
      (node (ref "D4") (pin "A") (pinfunction "A_A") (pintype "passive"))
      (node (ref "Q2") (pin "1") (pinfunction "SOURCE_1") (pintype "passive"))
      (node (ref "Q2") (pin "2") (pinfunction "SOURCE_2") (pintype "passive"))
      (node (ref "Q2") (pin "3") (pinfunction "SOURCE_3") (pintype "passive"))
      (node (ref "VD2") (pin "K") (pinfunction "K_K") (pintype "passive"))
    )
    (net (code "46") (name "Net-(D5-PA0)") (class "Default")
      (node (ref "D5") (pin "10") (pinfunction "PA0_10") (pintype "passive"))
      (node (ref "P6") (pin "1") (pinfunction "Pad_1") (pintype "passive"))
    )
    (net (code "47") (name "Net-(D5-PA1)") (class "Default")
      (node (ref "D5") (pin "11") (pinfunction "PA1_11") (pintype "passive"))
      (node (ref "P7") (pin "1") (pinfunction "Pad_1") (pintype "passive"))
    )
    (net (code "48") (name "Net-(D5-PA2)") (class "Default")
      (node (ref "D5") (pin "12") (pinfunction "PA2_12") (pintype "passive"))
      (node (ref "P8") (pin "1") (pinfunction "Pad_1") (pintype "passive"))
    )
    (net (code "49") (name "Net-(D5-PF0{slash}OSC_IN)") (class "Default")
      (node (ref "C28") (pin "1") (pinfunction "1_1") (pintype "passive"))
      (node (ref "D5") (pin "5") (pinfunction "PF0/OSC_IN_5") (pintype "passive"))
      (node (ref "X2") (pin "3") (pinfunction "3_3") (pintype "passive"))
    )
    (net (code "50") (name "Net-(D5-PF0{slash}OSC_OUT)") (class "Default")
      (node (ref "C25") (pin "1") (pinfunction "1_1") (pintype "passive"))
      (node (ref "D5") (pin "6") (pinfunction "PF0/OSC_OUT_6") (pintype "passive"))
      (node (ref "X2") (pin "1") (pinfunction "1_1") (pintype "passive"))
    )
    (net (code "51") (name "Net-(DA1-EN)") (class "Default")
      (node (ref "C2") (pin "2") (pinfunction "2_2") (pintype "passive"))
      (node (ref "DA1") (pin "4") (pinfunction "EN_4") (pintype "power_in"))
      (node (ref "DA1") (pin "5") (pinfunction "VIN_5") (pintype "passive"))
      (node (ref "L2") (pin "1") (pinfunction "1_1") (pintype "passive"))
      (node (ref "L3") (pin "1") (pinfunction "1_1") (pintype "passive"))
    )
    (net (code "52") (name "Net-(DA1-FB)") (class "Default")
      (node (ref "DA1") (pin "3") (pinfunction "FB_3") (pintype "power_in"))
      (node (ref "R4") (pin "2") (pinfunction "2_2") (pintype "passive"))
      (node (ref "R5") (pin "1") (pinfunction "1_1") (pintype "passive"))
      (node (ref "R6") (pin "2") (pinfunction "2_2") (pintype "passive"))
    )
    (net (code "53") (name "Net-(DA1-SW)") (class "Default")
      (node (ref "D2") (pin "A") (pinfunction "A_A") (pintype "passive"))
      (node (ref "DA1") (pin "1") (pinfunction "SW_1") (pintype "open_collector"))
      (node (ref "L3") (pin "2") (pinfunction "2_2") (pintype "passive"))
    )
    (net (code "54") (name "Net-(DA3-FILT)") (class "Default")
      (node (ref "C5") (pin "2") (pinfunction "2_2") (pintype "passive"))
      (node (ref "DA3") (pin "3") (pinfunction "FILT_3") (pintype "passive"))
    )
    (net (code "55") (name "Net-(DA3-VCC)") (class "Default")
      (node (ref "C1") (pin "2") (pinfunction "2_2") (pintype "passive"))
      (node (ref "C4") (pin "2") (pinfunction "2_2") (pintype "passive"))
      (node (ref "DA3") (pin "1") (pinfunction "VCC_1") (pintype "power_in"))
      (node (ref "L1") (pin "2") (pinfunction "2_2") (pintype "passive"))
    )
    (net (code "56") (name "Net-(DA4-V+)") (class "Default")
      (node (ref "C15") (pin "1") (pinfunction "1_1") (pintype "passive"))
      (node (ref "DA4") (pin "5") (pinfunction "V+_5") (pintype "power_in"))
      (node (ref "L7") (pin "2") (pinfunction "2_2") (pintype "passive"))
    )
    (net (code "57") (name "Net-(J1-PadS)") (class "Default")
      (node (ref "J1") (pin "S") (pinfunction "S_S") (pintype "passive"))
      (node (ref "R7") (pin "1") (pinfunction "1_1") (pintype "passive"))
    )
    (net (code "58") (name "Net-(J2-PadG)") (class "Default")
      (node (ref "J2") (pin "G") (pinfunction "G_G") (pintype "passive"))
      (node (ref "W3") (pin "2") (pinfunction "2_2") (pintype "passive"))
    )
    (net (code "59") (name "Net-(J2-PadS)") (class "Default")
      (node (ref "J2") (pin "S") (pinfunction "S_S") (pintype "passive"))
      (node (ref "R20") (pin "1") (pinfunction "1_1") (pintype "passive"))
    )
    (net (code "60") (name "Net-(L6-Pad2)") (class "Default")
      (node (ref "L6") (pin "2") (pinfunction "2_2") (pintype "passive"))
      (node (ref "R12") (pin "2") (pinfunction "2_2") (pintype "passive"))
    )
    (net (code "61") (name "Net-(L9-Pad1)") (class "Default")
      (node (ref "L9") (pin "1") (pinfunction "1_1") (pintype "passive"))
      (node (ref "R21") (pin "1") (pinfunction "1_1") (pintype "passive"))
      (node (ref "R30") (pin "1") (pinfunction "1_1") (pintype "passive"))
    )
    (net (code "62") (name "Net-(LED1-A)") (class "Default")
      (node (ref "LED1") (pin "1") (pinfunction "A_1") (pintype "passive"))
      (node (ref "R33") (pin "1") (pinfunction "1_1") (pintype "passive"))
    )
    (net (code "63") (name "Net-(Q1-DRAIN)") (class "Default")
      (node (ref "L5") (pin "2") (pinfunction "2_2") (pintype "passive"))
      (node (ref "Q1") (pin "3") (pinfunction "DRAIN_3") (pintype "passive"))
      (node (ref "VD1") (pin "A") (pinfunction "A_A") (pintype "passive"))
    )
    (net (code "64") (name "Net-(U1-VDD)") (class "Default")
      (node (ref "C16") (pin "2") (pinfunction "2_2") (pintype "passive"))
      (node (ref "L8") (pin "2") (pinfunction "2_2") (pintype "passive"))
      (node (ref "U1") (pin "1") (pinfunction "VDD_1") (pintype "power_in"))
    )
    (net (code "65") (name "TDC_VCC") (class "Default")
      (node (ref "C18") (pin "2") (pinfunction "2_2") (pintype "passive"))
      (node (ref "D3") (pin "14") (pinfunction "VCC_14") (pintype "passive"))
      (node (ref "D3") (pin "25") (pinfunction "EN_STOP2_25") (pintype "passive"))
      (node (ref "D3") (pin "26") (pinfunction "EN_STOP1_26") (pintype "passive"))
      (node (ref "D3") (pin "29") (pinfunction "VCC_29") (pintype "passive"))
      (node (ref "R30") (pin "2") (pinfunction "2_2") (pintype "passive"))
      (node (ref "R31") (pin "1") (pinfunction "1_1") (pintype "passive"))
    )
    (net (code "66") (name "VCC") (class "Default")
      (node (ref "C24") (pin "2") (pinfunction "2_2") (pintype "passive"))
      (node (ref "C27") (pin "2") (pinfunction "2_2") (pintype "passive"))
      (node (ref "C30") (pin "2") (pinfunction "2_2") (pintype "passive"))
      (node (ref "C31") (pin "2") (pinfunction "2_2") (pintype "passive"))
      (node (ref "C32") (pin "2") (pinfunction "2_2") (pintype "passive"))
      (node (ref "C7") (pin "2") (pinfunction "2_2") (pintype "passive"))
      (node (ref "D5") (pin "1") (pinfunction "VBAT_1") (pintype "passive"))
      (node (ref "D5") (pin "24") (pinfunction "VDD_24") (pintype "passive"))
      (node (ref "D5") (pin "36") (pinfunction "VDD_36") (pintype "passive"))
      (node (ref "D5") (pin "48") (pinfunction "VDD_48") (pintype "passive"))
      (node (ref "D5") (pin "9") (pinfunction "VDDA_9") (pintype "passive"))
      (node (ref "DA2") (pin "2") (pinfunction "VOUT_2") (pintype "power_in"))
      (node (ref "DA2") (pin "4") (pinfunction "VOUT_4") (pintype "power_in"))
      (node (ref "DA5") (pin "5") (pinfunction "V+_5") (pintype "power_in"))
      (node (ref "L1") (pin "1") (pinfunction "1_1") (pintype "passive"))
      (node (ref "L10") (pin "1") (pinfunction "1_1") (pintype "passive"))
      (node (ref "L7") (pin "1") (pinfunction "1_1") (pintype "passive"))
      (node (ref "L9") (pin "2") (pinfunction "2_2") (pintype "passive"))
      (node (ref "R25") (pin "1") (pinfunction "1_1") (pintype "passive"))
      (node (ref "R28") (pin "1") (pinfunction "1_1") (pintype "passive"))
    )
    (net (code "67") (name "Vin") (class "Default")
      (node (ref "C3") (pin "2") (pinfunction "2_2") (pintype "passive"))
      (node (ref "DA2") (pin "3") (pinfunction "VIN_3") (pintype "power_in"))
      (node (ref "L2") (pin "2") (pinfunction "2_2") (pintype "passive"))
      (node (ref "L4") (pin "1") (pinfunction "1_1") (pintype "passive"))
      (node (ref "P1") (pin "1") (pinfunction "47_1") (pintype "passive"))
    )
    (net (code "68") (name "Vlaser") (class "Default")
      (node (ref "C9") (pin "2") (pinfunction "2_2") (pintype "passive"))
      (node (ref "D2") (pin "K") (pinfunction "K_K") (pintype "passive"))
      (node (ref "L8") (pin "1") (pinfunction "1_1") (pintype "passive"))
      (node (ref "R18") (pin "2") (pinfunction "2_2") (pintype "passive"))
      (node (ref "R5") (pin "2") (pinfunction "2_2") (pintype "passive"))
    )
    (net (code "69") (name "unconnected-(D3-EN_START-Pad32)") (class "Default")
      (node (ref "D3") (pin "32") (pinfunction "EN_START_32") (pintype "passive"))
    )
    (net (code "70") (name "unconnected-(D3-FIRE_DOWN-Pad6)") (class "Default")
      (node (ref "D3") (pin "6") (pinfunction "FIRE_DOWN_6") (pintype "passive"))
    )
    (net (code "71") (name "unconnected-(D3-FIRE_IN-Pad7)") (class "Default")
      (node (ref "D3") (pin "7") (pinfunction "FIRE_IN_7") (pintype "passive"))
    )
    (net (code "72") (name "unconnected-(D3-LOADT-Pad18)") (class "Default")
      (node (ref "D3") (pin "18") (pinfunction "LOADT_18") (pintype "passive"))
    )
    (net (code "73") (name "unconnected-(D3-PT1-Pad24)") (class "Default")
      (node (ref "D3") (pin "24") (pinfunction "PT1_24") (pintype "passive"))
    )
    (net (code "74") (name "unconnected-(D3-PT2-Pad23)") (class "Default")
      (node (ref "D3") (pin "23") (pinfunction "PT2_23") (pintype "passive"))
    )
    (net (code "75") (name "unconnected-(D3-PT3-Pad20)") (class "Default")
      (node (ref "D3") (pin "20") (pinfunction "PT3_20") (pintype "passive"))
    )
    (net (code "76") (name "unconnected-(D3-PT4-Pad19)") (class "Default")
      (node (ref "D3") (pin "19") (pinfunction "PT4_19") (pintype "passive"))
    )
    (net (code "77") (name "unconnected-(D3-SENSET-Pad17)") (class "Default")
      (node (ref "D3") (pin "17") (pinfunction "SENSET_17") (pintype "passive"))
    )
    (net (code "78") (name "unconnected-(D3-XOUT-Pad2)") (class "Default")
      (node (ref "D3") (pin "2") (pinfunction "XOUT_2") (pintype "passive"))
    )
    (net (code "79") (name "unconnected-(D5-PA6-Pad16)") (class "Default")
      (node (ref "D5") (pin "16") (pinfunction "PA6_16") (pintype "passive"))
    )
    (net (code "80") (name "unconnected-(D5-PA11-Pad32)") (class "Default")
      (node (ref "D5") (pin "32") (pinfunction "PA11_32") (pintype "passive"))
    )
    (net (code "81") (name "unconnected-(D5-PA15-Pad38)") (class "Default")
      (node (ref "D5") (pin "38") (pinfunction "PA15_38") (pintype "passive"))
    )
    (net (code "82") (name "unconnected-(D5-PB0-Pad18)") (class "Default")
      (node (ref "D5") (pin "18") (pinfunction "PB0_18") (pintype "passive"))
    )
    (net (code "83") (name "unconnected-(D5-PB1-Pad19)") (class "Default")
      (node (ref "D5") (pin "19") (pinfunction "PB1_19") (pintype "passive"))
    )
    (net (code "84") (name "unconnected-(D5-PB5-Pad41)") (class "Default")
      (node (ref "D5") (pin "41") (pinfunction "PB5_41") (pintype "passive"))
    )
    (net (code "85") (name "unconnected-(D5-PB6-Pad42)") (class "Default")
      (node (ref "D5") (pin "42") (pinfunction "PB6_42") (pintype "passive"))
    )
    (net (code "86") (name "unconnected-(D5-PB7-Pad43)") (class "Default")
      (node (ref "D5") (pin "43") (pinfunction "PB7_43") (pintype "passive"))
    )
    (net (code "87") (name "unconnected-(D5-PB8-Pad45)") (class "Default")
      (node (ref "D5") (pin "45") (pinfunction "PB8_45") (pintype "passive"))
    )
    (net (code "88") (name "unconnected-(D5-PB9-Pad46)") (class "Default")
      (node (ref "D5") (pin "46") (pinfunction "PB9_46") (pintype "passive"))
    )
    (net (code "89") (name "unconnected-(D5-PB10-Pad21)") (class "Default")
      (node (ref "D5") (pin "21") (pinfunction "PB10_21") (pintype "passive"))
    )
    (net (code "90") (name "unconnected-(D5-PB11-Pad22)") (class "Default")
      (node (ref "D5") (pin "22") (pinfunction "PB11_22") (pintype "passive"))
    )
    (net (code "91") (name "unconnected-(D5-PC13-Pad2)") (class "Default")
      (node (ref "D5") (pin "2") (pinfunction "PC13_2") (pintype "passive"))
    )
    (net (code "92") (name "unconnected-(D5-PC14-Pad3)") (class "Default")
      (node (ref "D5") (pin "3") (pinfunction "PC14_3") (pintype "passive"))
    )
    (net (code "93") (name "unconnected-(D5-PC15-Pad4)") (class "Default")
      (node (ref "D5") (pin "4") (pinfunction "PC15_4") (pintype "passive"))
    )
    (net (code "94") (name "unconnected-(DA3-MON-Pad4)") (class "Default")
      (node (ref "DA3") (pin "4") (pinfunction "MON_4") (pintype "passive"))
    )
  )
)
